# Top.net
KiCad netlist of a schematic drawn in Altium Designer
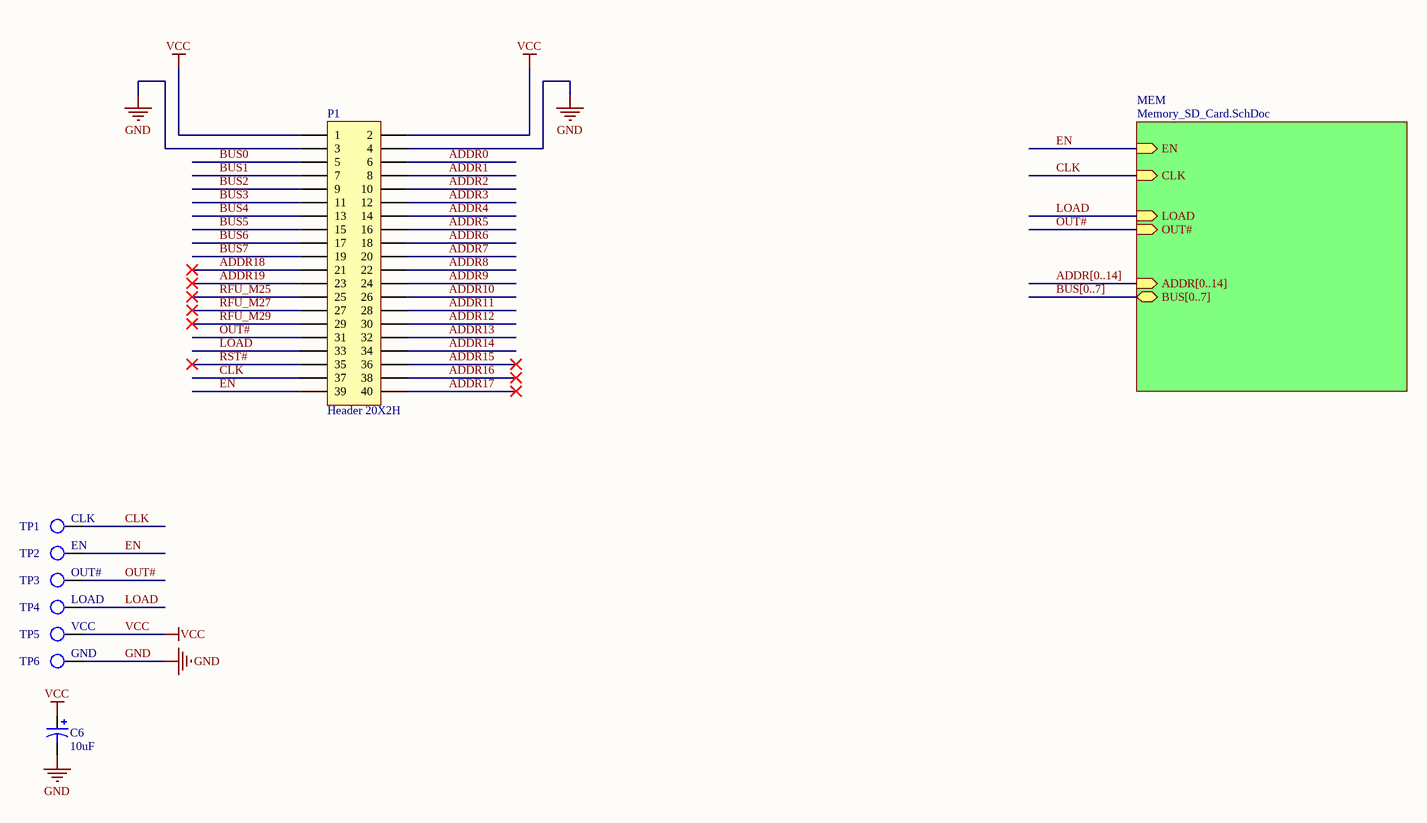
[diagram p0: Top.SchDoc]

(export (version "E")
  (design (tool "Eeschema 10.0.6"))
  (components
    (comp (ref "C6")
      (value "10uF")
      (footprint "C5x7")
      (description "Polarized Capacitor")
      (fields (field (name "Comment") "Cap Pol5") (field (name "PUBLISHER") "Altium Limited"))
      (libsource (lib "Miscellaneous Devices") (part "Cap Pol5"))
    )
    (comp (ref "P1")
      (value "Header 20X2H")
      (footprint "HDR2X20H")
      (description "Header, 20-Pin, Dual row, Right Angle")
      (fields (field (name "PUBLISHER") "Altium Limited"))
      (libsource (lib "Miscellaneous Connectors") (part "Header 20X2H"))
    )
    (comp (ref "TP1") (value "CLK") (footprint "KSTN-5011_V") (libsource (lib "TP") (part "TP")))
    (comp (ref "TP2") (value "EN") (footprint "KSTN-5011_V") (libsource (lib "TP") (part "TP")))
    (comp (ref "TP3") (value "OUT#") (footprint "KSTN-5011_V") (libsource (lib "TP") (part "TP")))
    (comp (ref "TP4") (value "LOAD") (footprint "KSTN-5011_V") (libsource (lib "TP") (part "TP")))
    (comp (ref "TP5") (value "VCC") (footprint "KSTN-5011_V") (libsource (lib "TP") (part "TP")))
    (comp (ref "TP6") (value "GND") (footprint "KSTN-5011_V") (libsource (lib "TP") (part "TP")))
  )
  (nets
    (net (code "1") (name "/ADDR0") (class "Default")
      (node (ref "P1") (pin "6") (pinfunction "6_6") (pintype "passive"))
    )
    (net (code "2") (name "/ADDR1") (class "Default")
      (node (ref "P1") (pin "8") (pinfunction "8_8") (pintype "passive"))
    )
    (net (code "3") (name "/ADDR2") (class "Default")
      (node (ref "P1") (pin "10") (pinfunction "10_10") (pintype "passive"))
    )
    (net (code "4") (name "/ADDR3") (class "Default")
      (node (ref "P1") (pin "12") (pinfunction "12_12") (pintype "passive"))
    )
    (net (code "5") (name "/ADDR4") (class "Default")
      (node (ref "P1") (pin "14") (pinfunction "14_14") (pintype "passive"))
    )
    (net (code "6") (name "/ADDR5") (class "Default")
      (node (ref "P1") (pin "16") (pinfunction "16_16") (pintype "passive"))
    )
    (net (code "7") (name "/ADDR6") (class "Default")
      (node (ref "P1") (pin "18") (pinfunction "18_18") (pintype "passive"))
    )
    (net (code "8") (name "/ADDR7") (class "Default")
      (node (ref "P1") (pin "20") (pinfunction "20_20") (pintype "passive"))
    )
    (net (code "9") (name "/ADDR8") (class "Default")
      (node (ref "P1") (pin "22") (pinfunction "22_22") (pintype "passive"))
    )
    (net (code "10") (name "/ADDR9") (class "Default")
      (node (ref "P1") (pin "24") (pinfunction "24_24") (pintype "passive"))
    )
    (net (code "11") (name "/ADDR10") (class "Default")
      (node (ref "P1") (pin "26") (pinfunction "26_26") (pintype "passive"))
    )
    (net (code "12") (name "/ADDR11") (class "Default")
      (node (ref "P1") (pin "28") (pinfunction "28_28") (pintype "passive"))
    )
    (net (code "13") (name "/ADDR12") (class "Default")
      (node (ref "P1") (pin "30") (pinfunction "30_30") (pintype "passive"))
    )
    (net (code "14") (name "/ADDR13") (class "Default")
      (node (ref "P1") (pin "32") (pinfunction "32_32") (pintype "passive"))
    )
    (net (code "15") (name "/ADDR14") (class "Default")
      (node (ref "P1") (pin "34") (pinfunction "34_34") (pintype "passive"))
    )
    (net (code "16") (name "/ADDR15") (class "Default")
      (node (ref "P1") (pin "36") (pinfunction "36_36") (pintype "passive+no_connect"))
    )
    (net (code "17") (name "/ADDR16") (class "Default")
      (node (ref "P1") (pin "38") (pinfunction "38_38") (pintype "passive+no_connect"))
    )
    (net (code "18") (name "/ADDR17") (class "Default")
      (node (ref "P1") (pin "40") (pinfunction "40_40") (pintype "passive+no_connect"))
    )
    (net (code "19") (name "/ADDR18") (class "Default")
      (node (ref "P1") (pin "21") (pinfunction "21_21") (pintype "passive+no_connect"))
    )
    (net (code "20") (name "/ADDR19") (class "Default")
      (node (ref "P1") (pin "23") (pinfunction "23_23") (pintype "passive+no_connect"))
    )
    (net (code "22") (name "/BUS0") (class "Default")
      (node (ref "P1") (pin "5") (pinfunction "5_5") (pintype "passive"))
    )
    (net (code "23") (name "/BUS1") (class "Default")
      (node (ref "P1") (pin "7") (pinfunction "7_7") (pintype "passive"))
    )
    (net (code "24") (name "/BUS2") (class "Default")
      (node (ref "P1") (pin "9") (pinfunction "9_9") (pintype "passive"))
    )
    (net (code "25") (name "/BUS3") (class "Default")
      (node (ref "P1") (pin "11") (pinfunction "11_11") (pintype "passive"))
    )
    (net (code "26") (name "/BUS4") (class "Default")
      (node (ref "P1") (pin "13") (pinfunction "13_13") (pintype "passive"))
    )
    (net (code "27") (name "/BUS5") (class "Default")
      (node (ref "P1") (pin "15") (pinfunction "15_15") (pintype "passive"))
    )
    (net (code "28") (name "/BUS6") (class "Default")
      (node (ref "P1") (pin "17") (pinfunction "17_17") (pintype "passive"))
    )
    (net (code "29") (name "/BUS7") (class "Default")
      (node (ref "P1") (pin "19") (pinfunction "19_19") (pintype "passive"))
    )
    (net (code "31") (name "/CLK") (class "Default")
      (node (ref "P1") (pin "37") (pinfunction "37_37") (pintype "passive"))
      (node (ref "TP1") (pin "1") (pintype "passive"))
    )
    (net (code "32") (name "/EN") (class "Default")
      (node (ref "P1") (pin "39") (pinfunction "39_39") (pintype "passive"))
      (node (ref "TP2") (pin "1") (pintype "passive"))
    )
    (net (code "33") (name "/LOAD") (class "Default")
      (node (ref "P1") (pin "33") (pinfunction "33_33") (pintype "passive"))
      (node (ref "TP4") (pin "1") (pintype "passive"))
    )
    (net (code "34") (name "/OUT#") (class "Default")
      (node (ref "P1") (pin "31") (pinfunction "31_31") (pintype "passive"))
      (node (ref "TP3") (pin "1") (pintype "passive"))
    )
    (net (code "35") (name "/RFU_M25") (class "Default")
      (node (ref "P1") (pin "25") (pinfunction "25_25") (pintype "passive+no_connect"))
    )
    (net (code "36") (name "/RFU_M27") (class "Default")
      (node (ref "P1") (pin "27") (pinfunction "27_27") (pintype "passive+no_connect"))
    )
    (net (code "37") (name "/RFU_M29") (class "Default")
      (node (ref "P1") (pin "29") (pinfunction "29_29") (pintype "passive+no_connect"))
    )
    (net (code "38") (name "/RST#") (class "Default")
      (node (ref "P1") (pin "35") (pinfunction "35_35") (pintype "passive+no_connect"))
    )
    (net (code "39") (name "GND") (class "Default")
      (node (ref "C6") (pin "2") (pinfunction "2_2") (pintype "passive"))
      (node (ref "P1") (pin "3") (pinfunction "3_3") (pintype "passive"))
      (node (ref "P1") (pin "4") (pinfunction "4_4") (pintype "passive"))
      (node (ref "TP6") (pin "1") (pintype "passive"))
    )
    (net (code "40") (name "VCC") (class "Default")
      (node (ref "C6") (pin "1") (pinfunction "1_1") (pintype "passive"))
      (node (ref "P1") (pin "1") (pinfunction "1_1") (pintype "passive"))
      (node (ref "P1") (pin "2") (pinfunction "2_2") (pintype "passive"))
      (node (ref "TP5") (pin "1") (pintype "passive"))
    )
  )
)
